# regulation.net
KiCad netlist of a schematic drawn in Altium Designer
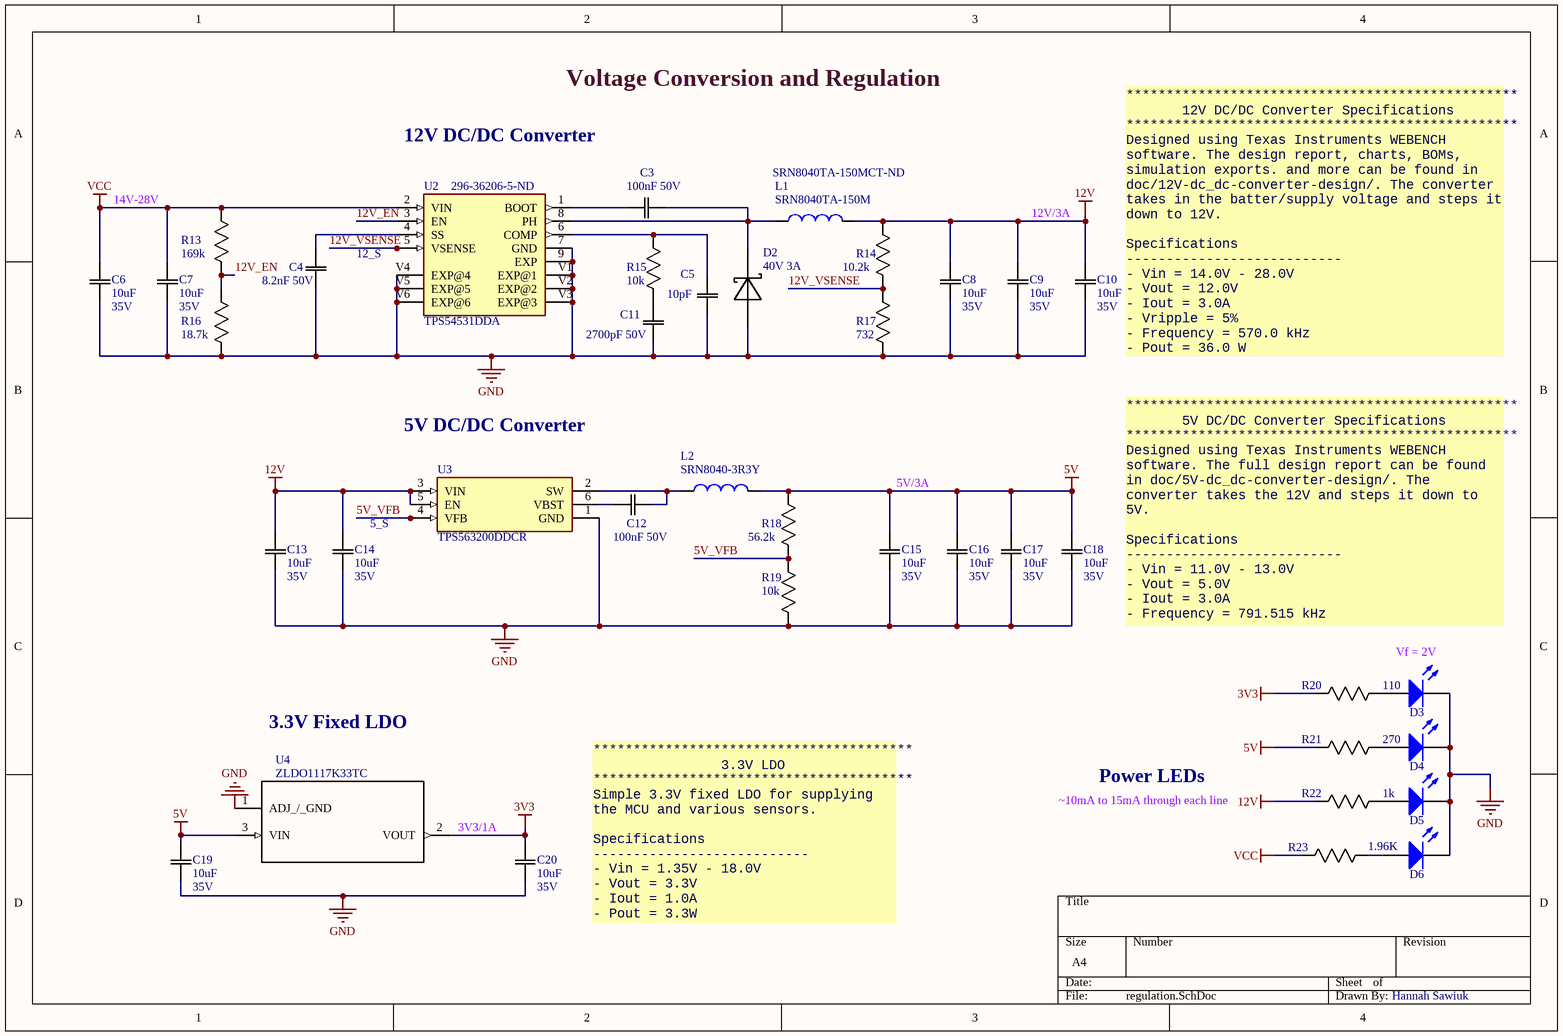
[diagram p0: regulation.SchDoc]

(export (version "E")
  (design (tool "Eeschema 10.0.6"))
  (components
    (comp (ref "5_S")
      (value "Test Point (Via)")
      (footprint "TP")
      (libsource (lib "AltiumLibraries") (part "Test Point (Via)"))
    )
    (comp (ref "12_S")
      (value "Test Point (Via)")
      (footprint "TP")
      (libsource (lib "AltiumLibraries") (part "Test Point (Via)"))
    )
    (comp (ref "C3")
      (value "100nF 50V")
      (footprint "0805")
      (description "CAP CER 0.1UF 50V X7R 0805")
      (fields (field (name "TOLERANCE") "10%"))
      (libsource (lib "AltiumLibraries") (part "CAP 100nF 50V"))
    )
    (comp (ref "C4")
      (value "8.2nF 50V")
      (footprint "0805")
      (description "CAP CER 8200PF 50V X7R 0805")
      (fields (field (name "TOLERANCE") "10%"))
      (libsource (lib "AltiumLibraries") (part "CAP 8.2nF 50V"))
    )
    (comp (ref "C5")
      (value "10pF")
      (footprint "0805")
      (description "CAP CER 10PF 50V X7R 0603/0805")
      (fields (field (name "TOLERANCE") "10%"))
      (libsource (lib "AltiumLibraries") (part "CAP 10pF 50V"))
    )
    (comp (ref "C6")
      (value "10uF")
      (footprint "0805")
      (description "CAP CER 10UF 35V X7R 0805")
      (fields (field (name "TOLERANCE") "10%") (field (name "RATING") "35V"))
      (libsource (lib "AltiumLibraries") (part "CAP 10uF 35V"))
    )
    (comp (ref "C7")
      (value "10uF")
      (footprint "0805")
      (description "CAP CER 10UF 35V X7R 0805")
      (fields (field (name "TOLERANCE") "10%") (field (name "RATING") "35V"))
      (libsource (lib "AltiumLibraries") (part "CAP 10uF 35V"))
    )
    (comp (ref "C8")
      (value "10uF")
      (footprint "0805")
      (description "CAP CER 10UF 35V X7R 0805")
      (fields (field (name "TOLERANCE") "10%") (field (name "RATING") "35V"))
      (libsource (lib "AltiumLibraries") (part "CAP 10uF 35V"))
    )
    (comp (ref "C9")
      (value "10uF")
      (footprint "0805")
      (description "CAP CER 10UF 35V X7R 0805")
      (fields (field (name "TOLERANCE") "10%") (field (name "RATING") "35V"))
      (libsource (lib "AltiumLibraries") (part "CAP 10uF 35V"))
    )
    (comp (ref "C10")
      (value "10uF")
      (footprint "0805")
      (description "CAP CER 10UF 35V X7R 0805")
      (fields (field (name "TOLERANCE") "10%") (field (name "RATING") "35V"))
      (libsource (lib "AltiumLibraries") (part "CAP 10uF 35V"))
    )
    (comp (ref "C11")
      (value "2700pF 50V")
      (footprint "0805")
      (description "CAP CER 2700PF 50V X7R 0805")
      (fields (field (name "TOLERANCE") "10%"))
      (libsource (lib "AltiumLibraries") (part "CAP 2700pF 50V"))
    )
    (comp (ref "C12")
      (value "100nF 50V")
      (footprint "0805")
      (description "CAP CER 0.1UF 50V X7R 0805")
      (fields (field (name "TOLERANCE") "10%"))
      (libsource (lib "AltiumLibraries") (part "CAP 100nF 50V"))
    )
    (comp (ref "C13")
      (value "10uF")
      (footprint "0805")
      (description "CAP CER 10UF 35V X7R 0805")
      (fields (field (name "TOLERANCE") "10%") (field (name "RATING") "35V"))
      (libsource (lib "AltiumLibraries") (part "CAP 10uF 35V"))
    )
    (comp (ref "C14")
      (value "10uF")
      (footprint "0805")
      (description "CAP CER 10UF 35V X7R 0805")
      (fields (field (name "TOLERANCE") "10%") (field (name "RATING") "35V"))
      (libsource (lib "AltiumLibraries") (part "CAP 10uF 35V"))
    )
    (comp (ref "C15")
      (value "10uF")
      (footprint "0805")
      (description "CAP CER 10UF 35V X7R 0805")
      (fields (field (name "TOLERANCE") "10%") (field (name "RATING") "35V"))
      (libsource (lib "AltiumLibraries") (part "CAP 10uF 35V"))
    )
    (comp (ref "C16")
      (value "10uF")
      (footprint "0805")
      (description "CAP CER 10UF 35V X7R 0805")
      (fields (field (name "TOLERANCE") "10%") (field (name "RATING") "35V"))
      (libsource (lib "AltiumLibraries") (part "CAP 10uF 35V"))
    )
    (comp (ref "C17")
      (value "10uF")
      (footprint "0805")
      (description "CAP CER 10UF 35V X7R 0805")
      (fields (field (name "TOLERANCE") "10%") (field (name "RATING") "35V"))
      (libsource (lib "AltiumLibraries") (part "CAP 10uF 35V"))
    )
    (comp (ref "C18")
      (value "10uF")
      (footprint "0805")
      (description "CAP CER 10UF 35V X7R 0805")
      (fields (field (name "TOLERANCE") "10%") (field (name "RATING") "35V"))
      (libsource (lib "AltiumLibraries") (part "CAP 10uF 35V"))
    )
    (comp (ref "C19")
      (value "10uF")
      (footprint "0805")
      (description "CAP CER 10UF 35V X7R 0805")
      (fields (field (name "TOLERANCE") "10%") (field (name "RATING") "35V"))
      (libsource (lib "AltiumLibraries") (part "CAP 10uF 35V"))
    )
    (comp (ref "C20")
      (value "10uF")
      (footprint "0805")
      (description "CAP CER 10UF 35V X7R 0805")
      (fields (field (name "TOLERANCE") "10%") (field (name "RATING") "35V"))
      (libsource (lib "AltiumLibraries") (part "CAP 10uF 35V"))
    )
    (comp (ref "D2")
      (value "40V 3A")
      (footprint "DO-214AC")
      (description "Diode Schottky 40V 3A Surface Mount SMA")
      (libsource (lib "AltiumLibraries") (part "DIODE SCHOTTKY 40V 3A"))
    )
    (comp (ref "D3")
      (value "LED2")
      (footprint "3.2X1.6X1.1")
      (description "Typical RED, GREEN, YELLOW, AMBER GaAs LED")
      (libsource (lib "AltiumLibraries") (part "LED GREEN SMD"))
    )
    (comp (ref "D4")
      (value "LED2")
      (footprint "3.2X1.6X1.1")
      (description "Typical RED, GREEN, YELLOW, AMBER GaAs LED")
      (libsource (lib "AltiumLibraries") (part "LED GREEN SMD"))
    )
    (comp (ref "D5")
      (value "LED2")
      (footprint "3.2X1.6X1.1")
      (description "Typical RED, GREEN, YELLOW, AMBER GaAs LED")
      (libsource (lib "AltiumLibraries") (part "LED GREEN SMD"))
    )
    (comp (ref "D6")
      (value "LED2")
      (footprint "3.2X1.6X1.1")
      (description "Typical RED, GREEN, YELLOW, AMBER GaAs LED")
      (libsource (lib "AltiumLibraries") (part "LED GREEN SMD"))
    )
    (comp (ref "L1")
      (value "SRN8040TA-150M")
      (footprint "INDP8279X40M")
      (description "15µH Semi-Shielded Wirewound Inductor 2.4A 70mOhm Max Nonstandard")
      (fields (field (name "MF") "Bourns Inc.") (field (name "SUPPLIER PART NUMBER 1") "SRN8040TA-150MCT-ND"))
      (libsource (lib "AltiumLibraries") (part "IND 15UH 3.2A 50 MOHM"))
    )
    (comp (ref "L2")
      (value "SRN8040-3R3Y")
      (footprint "INDP8279X40M")
      (description "3.3µH Semi-Shielded Wirewound Inductor 5.6A 21mOhm Max Nonstandard")
      (fields (field (name "MF") "Bourns Inc."))
      (libsource (lib "AltiumLibraries") (part "IND 3.3UH 5.6A 21 MOHM SMD"))
    )
    (comp (ref "R13")
      (value "169k")
      (footprint "0805")
      (description "RES SMD 169K OHM 1% 1/8W 0805")
      (fields (field (name "TOLERANCE") "1%"))
      (libsource (lib "AltiumLibraries") (part "RES 169k 1/8W"))
    )
    (comp (ref "R14")
      (value "10.2k")
      (footprint "0805")
      (description "RES SMD 10.2K OHM 1% 1/8W 0805")
      (fields (field (name "TOLERANCE") "1%"))
      (libsource (lib "AltiumLibraries") (part "RES 10.2k 1/8W"))
    )
    (comp (ref "R15")
      (value "10k")
      (footprint "0805")
      (description "RES SMD 10K OHM 1% 1/8W 0805")
      (fields (field (name "TOLERANCE") "1%"))
      (libsource (lib "AltiumLibraries") (part "RES 10k 1/8W - 1%"))
    )
    (comp (ref "R16")
      (value "18.7k")
      (footprint "0805")
      (description "RES SMD 18.7K OHM 1% 1/8W 0805")
      (fields (field (name "TOLERANCE") "1%"))
      (libsource (lib "AltiumLibraries") (part "RES 18.7K 1/8W"))
    )
    (comp (ref "R17")
      (value "732")
      (footprint "0805")
      (description "RES SMD 732 OHM 1% 1/8W 0805")
      (fields (field (name "TOLERANCE") "1%"))
      (libsource (lib "AltiumLibraries") (part "RES 732.0 1/8W"))
    )
    (comp (ref "R18")
      (value "56.2k")
      (footprint "0805")
      (description "RES SMD 56.2K OHM 1% 1/10W 0603")
      (fields (field (name "TOLERANCE") "1%"))
      (libsource (lib "AltiumLibraries") (part "RES 56.2k 1/10W"))
    )
    (comp (ref "R19")
      (value "10k")
      (footprint "0805")
      (description "RES SMD 10K OHM 1% 1/8W 0805")
      (fields (field (name "TOLERANCE") "1%"))
      (libsource (lib "AltiumLibraries") (part "RES 10k 1/8W - 1%"))
    )
    (comp (ref "R20")
      (value "110")
      (footprint "0805")
      (description "RES SMD 110 OHM 1% 1/8W 0805")
      (fields (field (name "TOLERANCE") "1%"))
      (libsource (lib "AltiumLibraries") (part "RES 110.0 1/8W - 1%"))
    )
    (comp (ref "R21")
      (value "270")
      (footprint "0805")
      (description "RES SMD 270 OHM 5% 1/8W 0805")
      (fields (field (name "TOLERANCE") "5%"))
      (libsource (lib "AltiumLibraries") (part "RES 270.0 1/8W"))
    )
    (comp (ref "R22")
      (value "1k")
      (footprint "0805")
      (description "RES SMD 1K OHM 5% 1/8W 0805")
      (fields (field (name "TOLERANCE") "5%"))
      (libsource (lib "AltiumLibraries") (part "RES 1k 1/8W"))
    )
    (comp (ref "R23")
      (value "1.96K")
      (footprint "0805")
      (description "RES SMD 1.96K OHM 1% 1/8W 0805")
      (fields (field (name "TOLERANCE") "1%"))
      (libsource (lib "AltiumLibraries") (part "RES 1.96k 1/8W"))
    )
    (comp (ref "U2")
      (value "TPS54531DDA")
      (footprint "8-PowerSOIC")
      (description "Buck Switching Regulator IC Positive Adjustable 0.8V 1 Output 5A 8-PowerSOIC _0.154, 3.90mm Width_")
      (fields
        (field (name "MF") "Texas Instruments")
        (field (name "SUPPLIER PART NUMBER 1") "296-36206-5-ND")
      )
      (libsource (lib "AltiumLibraries") (part "TPS54531DDA"))
    )
    (comp (ref "U3")
      (value "TPS563200DDCR")
      (footprint "TSOT-23-6")
      (description "Buck Switching Regulator IC Positive Adjustable 0.76V 1 Output 3A SOT-23-6 Thin, TSOT-23-6")
      (fields (field (name "MF") "Texas Instruments"))
      (libsource (lib "AltiumLibraries") (part "TPS563200DDCR"))
    )
    (comp (ref "U4")
      (value "ZLDO1117K33TC")
      (footprint "DPAK (TO-252)")
      (description "Linear Voltage Regulator IC Positive Fixed 1 Output  1A TO-252-3")
      (fields (field (name "MF") "Diodes Incorporated"))
      (libsource (lib "AltiumLibraries") (part "ZLDO1117K33TC"))
    )
  )
  (nets
    (net (code "1") (name "/5V_VFB") (class "Default")
      (node (ref "5_S") (pin "1") (pinfunction "1_1") (pintype "passive"))
      (node (ref "R18") (pin "2") (pinfunction "R2_2") (pintype "passive"))
      (node (ref "R19") (pin "2") (pinfunction "R2_2") (pintype "passive"))
      (node (ref "U3") (pin "4") (pinfunction "VFB_4") (pintype "input"))
    )
    (net (code "2") (name "/12V_EN") (class "Default")
      (node (ref "R13") (pin "2") (pinfunction "R2_2") (pintype "passive"))
      (node (ref "R16") (pin "1") (pinfunction "R1_1") (pintype "passive"))
      (node (ref "U2") (pin "3") (pinfunction "EN_3") (pintype "input"))
    )
    (net (code "3") (name "/12V_VSENSE") (class "Default")
      (node (ref "12_S") (pin "1") (pinfunction "1_1") (pintype "passive"))
      (node (ref "R14") (pin "1") (pinfunction "R1_1") (pintype "passive"))
      (node (ref "R17") (pin "2") (pinfunction "R2_2") (pintype "passive"))
      (node (ref "U2") (pin "5") (pinfunction "VSENSE_5") (pintype "input"))
    )
    (net (code "4") (name "3V3") (class "Default")
      (node (ref "C20") (pin "1") (pinfunction "C1_1") (pintype "passive"))
      (node (ref "R20") (pin "1") (pinfunction "R1_1") (pintype "passive"))
      (node (ref "U4") (pin "2") (pinfunction "VOUT_2") (pintype "output"))
    )
    (net (code "5") (name "5V") (class "Default")
      (node (ref "C15") (pin "1") (pinfunction "C1_1") (pintype "passive"))
      (node (ref "C16") (pin "1") (pinfunction "C1_1") (pintype "passive"))
      (node (ref "C17") (pin "1") (pinfunction "C1_1") (pintype "passive"))
      (node (ref "C18") (pin "1") (pinfunction "C1_1") (pintype "passive"))
      (node (ref "C19") (pin "1") (pinfunction "C1_1") (pintype "passive"))
      (node (ref "L2") (pin "2") (pinfunction "2_2") (pintype "passive"))
      (node (ref "R18") (pin "1") (pinfunction "R1_1") (pintype "passive"))
      (node (ref "R21") (pin "1") (pinfunction "R1_1") (pintype "passive"))
      (node (ref "U4") (pin "3") (pinfunction "VIN_3") (pintype "input"))
    )
    (net (code "6") (name "12V") (class "Default")
      (node (ref "C10") (pin "1") (pinfunction "C1_1") (pintype "passive"))
      (node (ref "C13") (pin "1") (pinfunction "C1_1") (pintype "passive"))
      (node (ref "C14") (pin "1") (pinfunction "C1_1") (pintype "passive"))
      (node (ref "C8") (pin "1") (pinfunction "C1_1") (pintype "passive"))
      (node (ref "C9") (pin "1") (pinfunction "C1_1") (pintype "passive"))
      (node (ref "L1") (pin "2") (pinfunction "2_2") (pintype "passive"))
      (node (ref "R14") (pin "2") (pinfunction "R2_2") (pintype "passive"))
      (node (ref "R22") (pin "1") (pinfunction "R1_1") (pintype "passive"))
      (node (ref "U3") (pin "3") (pinfunction "VIN_3") (pintype "input"))
      (node (ref "U3") (pin "5") (pinfunction "EN_5") (pintype "input"))
    )
    (net (code "7") (name "GND") (class "Default")
      (node (ref "C10") (pin "2") (pinfunction "C2_2") (pintype "passive"))
      (node (ref "C11") (pin "1") (pinfunction "C1_1") (pintype "passive"))
      (node (ref "C13") (pin "2") (pinfunction "C2_2") (pintype "passive"))
      (node (ref "C14") (pin "2") (pinfunction "C2_2") (pintype "passive"))
      (node (ref "C15") (pin "2") (pinfunction "C2_2") (pintype "passive"))
      (node (ref "C16") (pin "2") (pinfunction "C2_2") (pintype "passive"))
      (node (ref "C17") (pin "2") (pinfunction "C2_2") (pintype "passive"))
      (node (ref "C18") (pin "2") (pinfunction "C2_2") (pintype "passive"))
      (node (ref "C19") (pin "2") (pinfunction "C2_2") (pintype "passive"))
      (node (ref "C20") (pin "2") (pinfunction "C2_2") (pintype "passive"))
      (node (ref "C4") (pin "1") (pinfunction "C1_1") (pintype "passive"))
      (node (ref "C5") (pin "1") (pinfunction "C1_1") (pintype "passive"))
      (node (ref "C6") (pin "2") (pinfunction "C2_2") (pintype "passive"))
      (node (ref "C7") (pin "2") (pinfunction "C2_2") (pintype "passive"))
      (node (ref "C8") (pin "2") (pinfunction "C2_2") (pintype "passive"))
      (node (ref "C9") (pin "2") (pinfunction "C2_2") (pintype "passive"))
      (node (ref "D2") (pin "A") (pinfunction "A_A") (pintype "passive"))
      (node (ref "D3") (pin "2") (pinfunction "K_2") (pintype "passive"))
      (node (ref "D4") (pin "2") (pinfunction "K_2") (pintype "passive"))
      (node (ref "D5") (pin "2") (pinfunction "K_2") (pintype "passive"))
      (node (ref "D6") (pin "2") (pinfunction "K_2") (pintype "passive"))
      (node (ref "R16") (pin "2") (pinfunction "R2_2") (pintype "passive"))
      (node (ref "R17") (pin "1") (pinfunction "R1_1") (pintype "passive"))
      (node (ref "R19") (pin "1") (pinfunction "R1_1") (pintype "passive"))
      (node (ref "U2") (pin "7") (pinfunction "GND_7") (pintype "power_in"))
      (node (ref "U2") (pin "9") (pinfunction "EXP_9") (pintype "power_in"))
      (node (ref "U2") (pin "V1") (pinfunction "EXP@1_V1") (pintype "power_in"))
      (node (ref "U2") (pin "V2") (pinfunction "EXP@2_V2") (pintype "power_in"))
      (node (ref "U2") (pin "V3") (pinfunction "EXP@3_V3") (pintype "power_in"))
      (node (ref "U2") (pin "V4") (pinfunction "EXP@4_V4") (pintype "power_in"))
      (node (ref "U2") (pin "V5") (pinfunction "EXP@5_V5") (pintype "power_in"))
      (node (ref "U2") (pin "V6") (pinfunction "EXP@6_V6") (pintype "power_in"))
      (node (ref "U3") (pin "1") (pinfunction "GND_1") (pintype "power_in"))
      (node (ref "U4") (pin "1") (pinfunction "ADJ_/_GND_1") (pintype "power_in"))
    )
    (net (code "8") (name "Net-(C3-C1)") (class "Default")
      (node (ref "C3") (pin "1") (pinfunction "C1_1") (pintype "passive"))
      (node (ref "U2") (pin "1") (pinfunction "BOOT_1") (pintype "output"))
    )
    (net (code "9") (name "Net-(C3-C2)") (class "Default")
      (node (ref "C3") (pin "2") (pinfunction "C2_2") (pintype "passive"))
      (node (ref "D2") (pin "C") (pinfunction "K_C") (pintype "passive"))
      (node (ref "L1") (pin "1") (pinfunction "1_1") (pintype "passive"))
      (node (ref "U2") (pin "8") (pinfunction "PH_8") (pintype "output"))
    )
    (net (code "10") (name "Net-(C4-C2)") (class "Default")
      (node (ref "C4") (pin "2") (pinfunction "C2_2") (pintype "passive"))
      (node (ref "U2") (pin "4") (pinfunction "SS_4") (pintype "input"))
    )
    (net (code "11") (name "Net-(C5-C2)") (class "Default")
      (node (ref "C5") (pin "2") (pinfunction "C2_2") (pintype "passive"))
      (node (ref "R15") (pin "1") (pinfunction "R1_1") (pintype "passive"))
      (node (ref "U2") (pin "6") (pinfunction "COMP_6") (pintype "output"))
    )
    (net (code "12") (name "Net-(C11-C2)") (class "Default")
      (node (ref "C11") (pin "2") (pinfunction "C2_2") (pintype "passive"))
      (node (ref "R15") (pin "2") (pinfunction "R2_2") (pintype "passive"))
    )
    (net (code "13") (name "Net-(C12-C1)") (class "Default")
      (node (ref "C12") (pin "1") (pinfunction "C1_1") (pintype "passive"))
      (node (ref "U3") (pin "6") (pinfunction "VBST_6") (pintype "passive"))
    )
    (net (code "14") (name "Net-(C12-C2)") (class "Default")
      (node (ref "C12") (pin "2") (pinfunction "C2_2") (pintype "passive"))
      (node (ref "L2") (pin "1") (pinfunction "1_1") (pintype "passive"))
      (node (ref "U3") (pin "2") (pinfunction "SW_2") (pintype "passive"))
    )
    (net (code "15") (name "Net-(D3-A)") (class "Default")
      (node (ref "D3") (pin "1") (pinfunction "A_1") (pintype "passive"))
      (node (ref "R20") (pin "2") (pinfunction "R2_2") (pintype "passive"))
    )
    (net (code "16") (name "Net-(D4-A)") (class "Default")
      (node (ref "D4") (pin "1") (pinfunction "A_1") (pintype "passive"))
      (node (ref "R21") (pin "2") (pinfunction "R2_2") (pintype "passive"))
    )
    (net (code "17") (name "Net-(D5-A)") (class "Default")
      (node (ref "D5") (pin "1") (pinfunction "A_1") (pintype "passive"))
      (node (ref "R22") (pin "2") (pinfunction "R2_2") (pintype "passive"))
    )
    (net (code "18") (name "Net-(D6-A)") (class "Default")
      (node (ref "D6") (pin "1") (pinfunction "A_1") (pintype "passive"))
      (node (ref "R23") (pin "2") (pinfunction "R2_2") (pintype "passive"))
    )
    (net (code "19") (name "VCC") (class "Default")
      (node (ref "C6") (pin "1") (pinfunction "C1_1") (pintype "passive"))
      (node (ref "C7") (pin "1") (pinfunction "C1_1") (pintype "passive"))
      (node (ref "R13") (pin "1") (pinfunction "R1_1") (pintype "passive"))
      (node (ref "R23") (pin "1") (pinfunction "R1_1") (pintype "passive"))
      (node (ref "U2") (pin "2") (pinfunction "VIN_2") (pintype "input"))
    )
  )
)
